# source_eagle.net
KiCad netlist of a schematic drawn in EAGLE
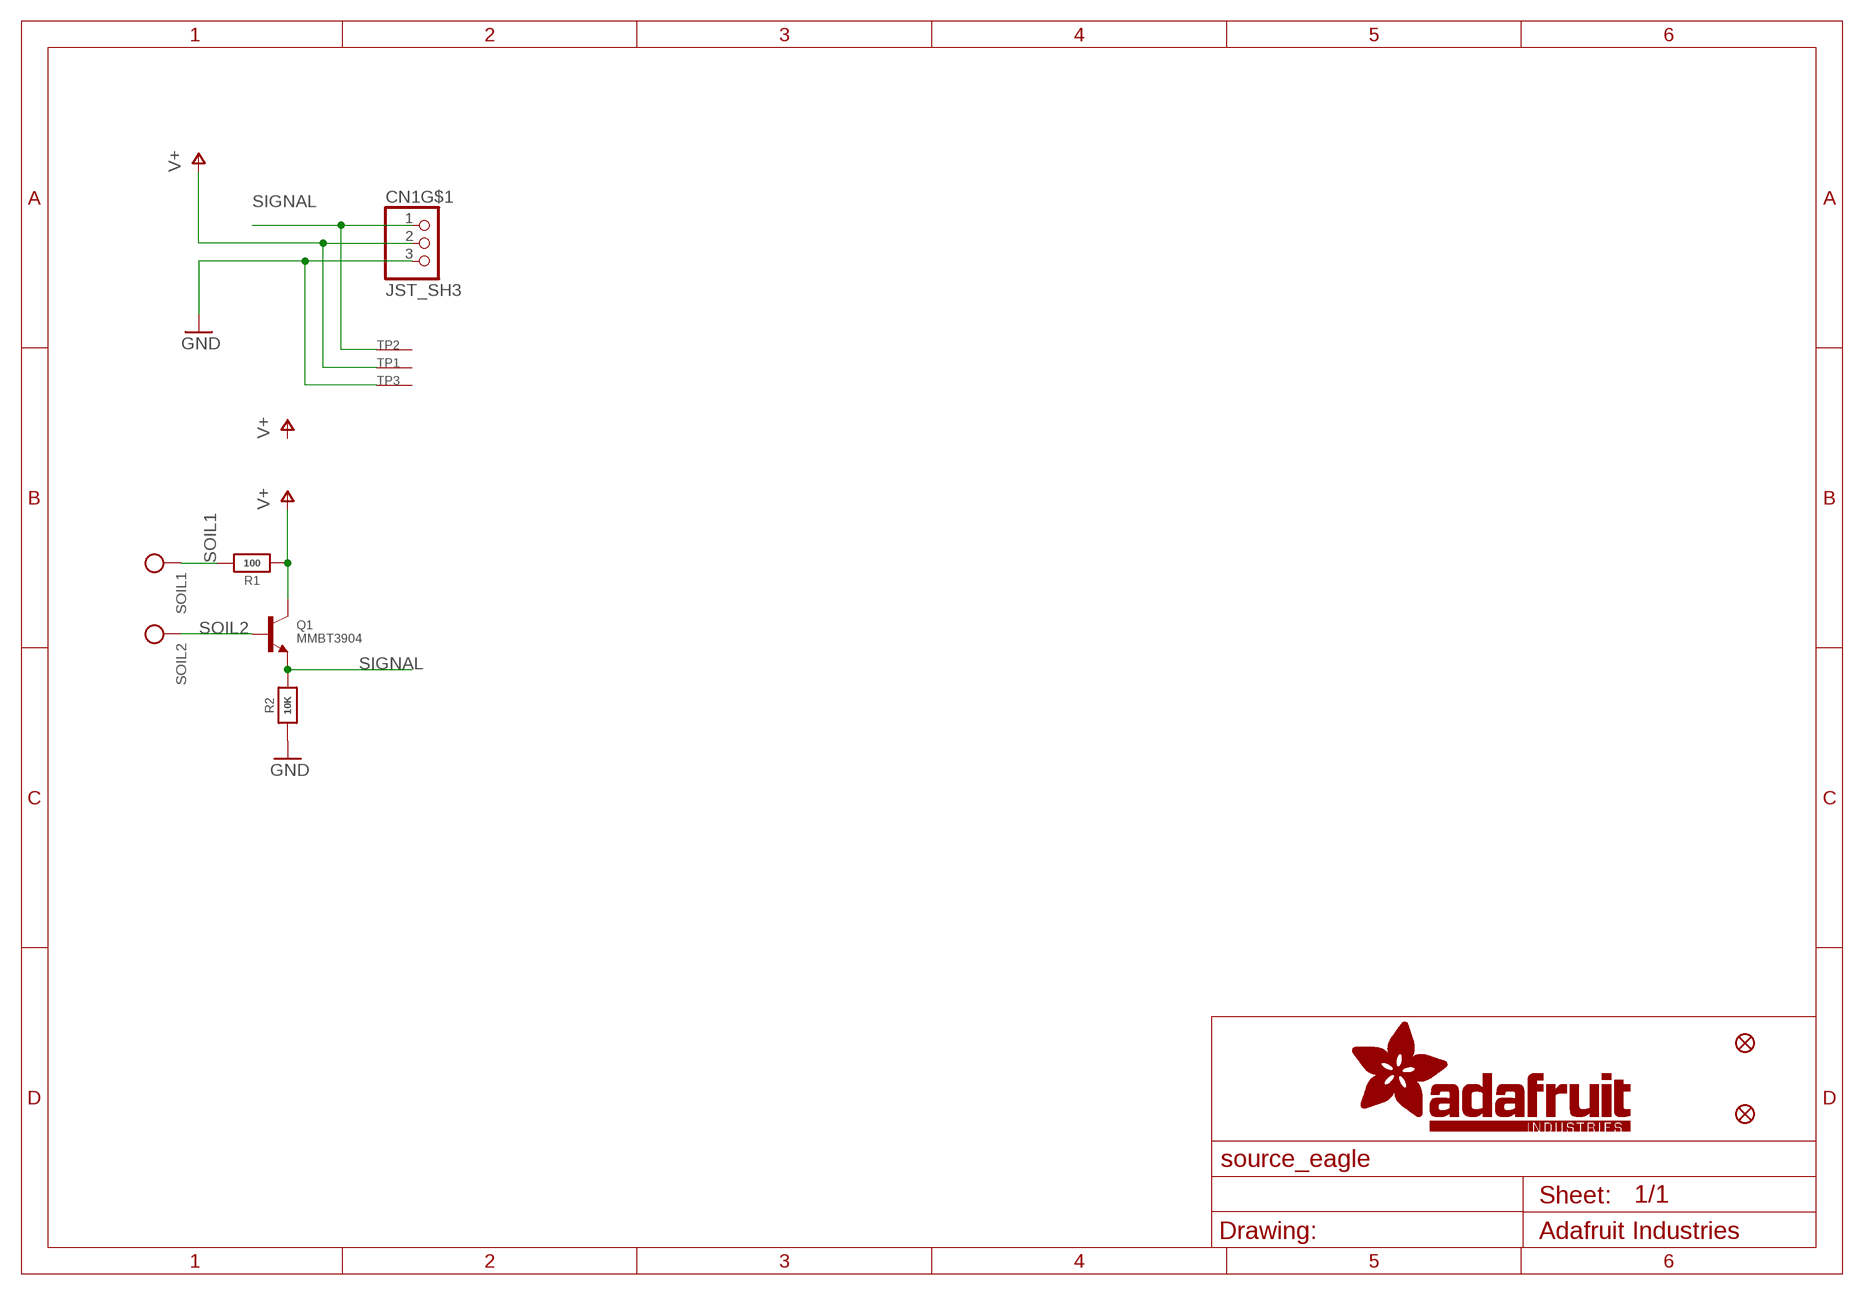
[diagram p0: schematic, sheet 1]

(export (version "E")
  (design (tool "Eeschema 10.0.6"))
  (components
    (comp (ref "CN1")
      (value "JST_SH3")
      (footprint "eagle-import:JST_SH3")
      (libsource (lib "eagle-import") (part "CON_JST_SH_3PINHORZ"))
    )
    (comp (ref "Q1")
      (value "MMBT3904")
      (footprint "eagle-import:SOT23-WIDE")
      (libsource (lib "eagle-import") (part "TRANSISTOR_NPNWIDE"))
    )
    (comp (ref "R1")
      (value "100")
      (footprint "eagle-import:0805-NO")
      (libsource (lib "eagle-import") (part "RESISTOR0805_NOOUTLINE"))
    )
    (comp (ref "R2")
      (value "10K")
      (footprint "eagle-import:0805-NO")
      (libsource (lib "eagle-import") (part "RESISTOR0805_NOOUTLINE"))
    )
    (comp (ref "SOIL1")
      (value "TESTPOINTROUND2MMNO")
      (footprint "eagle-import:TESTPOINT_ROUND_2MM_NO")
      (libsource (lib "eagle-import") (part "TESTPOINTROUND2MMNO"))
    )
    (comp (ref "SOIL2")
      (value "TESTPOINTROUND2MMNO")
      (footprint "eagle-import:TESTPOINT_ROUND_2MM_NO")
      (libsource (lib "eagle-import") (part "TESTPOINTROUND2MMNO"))
    )
    (comp (ref "TP1")
      (value "SEWTAPPCB_ALLIGATOR")
      (footprint "eagle-import:PCB_ALLI")
      (libsource (lib "eagle-import") (part "SEWTAPPCB_ALLIGATOR"))
    )
    (comp (ref "TP2")
      (value "SEWTAPPCB_ALLIGATOR")
      (footprint "eagle-import:PCB_ALLI")
      (libsource (lib "eagle-import") (part "SEWTAPPCB_ALLIGATOR"))
    )
    (comp (ref "TP3")
      (value "SEWTAPPCB_ALLIGATOR")
      (footprint "eagle-import:PCB_ALLI")
      (libsource (lib "eagle-import") (part "SEWTAPPCB_ALLIGATOR"))
    )
    (comp (ref "U$2")
      (value "FIDUCIAL_0.5MM")
      (footprint "eagle-import:FIDUCIAL_0.5MM")
      (libsource (lib "eagle-import") (part "FIDUCIAL_0.5MM"))
    )
    (comp (ref "U$3")
      (value "FIDUCIAL_0.5MM")
      (footprint "eagle-import:FIDUCIAL_0.5MM")
      (libsource (lib "eagle-import") (part "FIDUCIAL_0.5MM"))
    )
  )
  (nets
    (net (code "1") (name "/SIGNAL") (class "Default")
      (node (ref "CN1") (pin "1") (pinfunction "1_1") (pintype "passive"))
      (node (ref "Q1") (pin "2") (pinfunction "E_2") (pintype "passive"))
      (node (ref "R2") (pin "2") (pinfunction "2_2") (pintype "passive"))
      (node (ref "TP2") (pin "P$1") (pinfunction "SEW_P$1") (pintype "bidirectional"))
    )
    (net (code "2") (name "/SOIL1") (class "Default")
      (node (ref "R1") (pin "2") (pinfunction "2_2") (pintype "passive"))
      (node (ref "SOIL1") (pin "P$1") (pinfunction "P$1_P$1") (pintype "bidirectional"))
    )
    (net (code "3") (name "/SOIL2") (class "Default")
      (node (ref "Q1") (pin "1") (pinfunction "B_1") (pintype "passive"))
      (node (ref "SOIL2") (pin "P$1") (pinfunction "P$1_P$1") (pintype "bidirectional"))
    )
    (net (code "4") (name "GND") (class "Default")
      (node (ref "CN1") (pin "3") (pinfunction "3_3") (pintype "passive"))
      (node (ref "R2") (pin "1") (pinfunction "1_1") (pintype "passive"))
      (node (ref "TP3") (pin "P$1") (pinfunction "SEW_P$1") (pintype "bidirectional"))
    )
    (net (code "5") (name "V+") (class "Default")
      (node (ref "CN1") (pin "2") (pinfunction "2_2") (pintype "passive"))
      (node (ref "Q1") (pin "3") (pinfunction "C_3") (pintype "passive"))
      (node (ref "R1") (pin "1") (pinfunction "1_1") (pintype "passive"))
      (node (ref "TP1") (pin "P$1") (pinfunction "SEW_P$1") (pintype "bidirectional"))
    )
  )
)
